# remote-camera.net
KiCad netlist of a schematic drawn in EAGLE
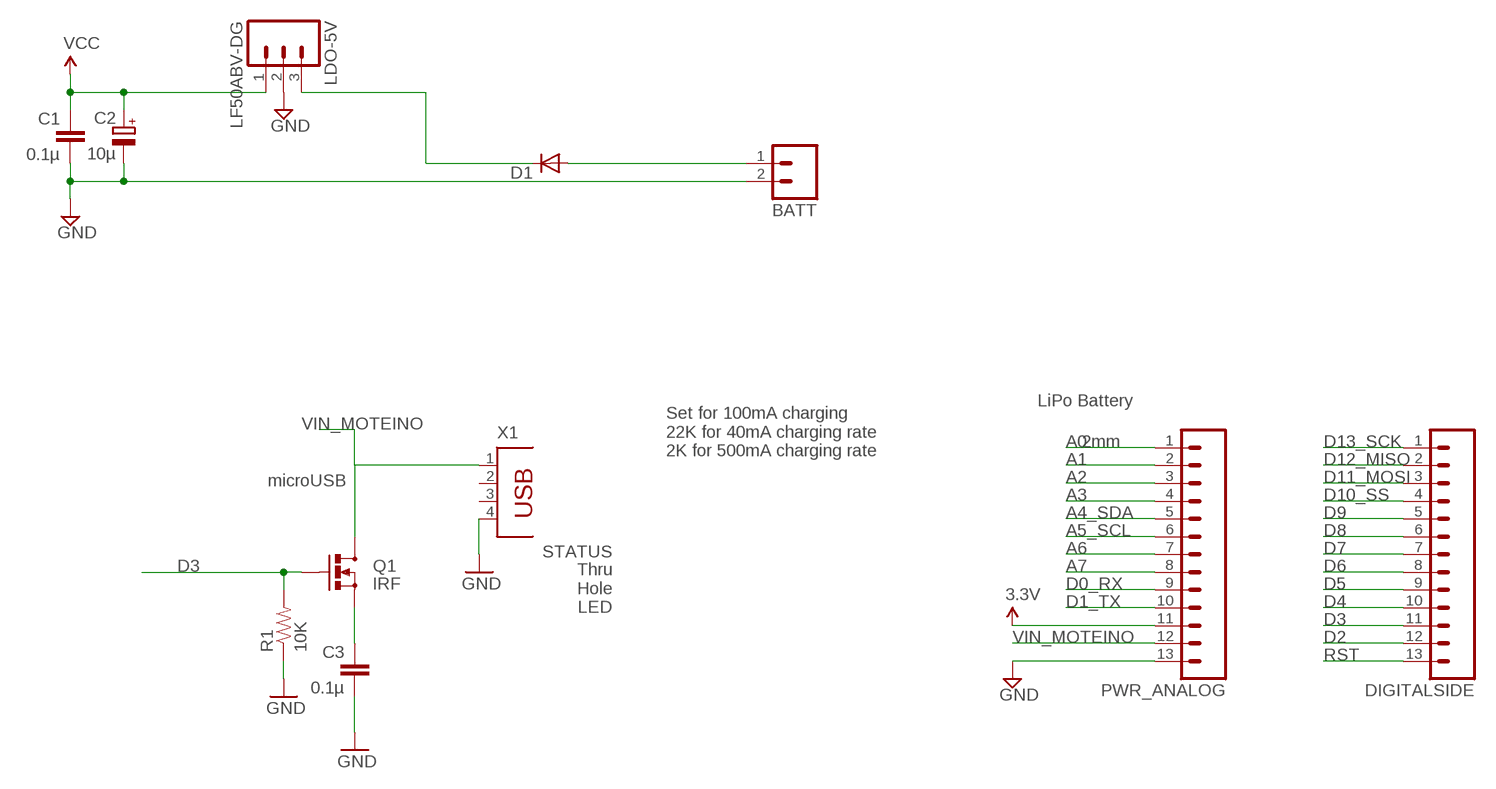
[diagram p0: schematic, sheet 1]

(export (version "E")
  (design (tool "Eeschema 10.0.6"))
  (components
    (comp (ref "BATT")
      (value "M02PTH")
      (footprint "eagle-import:1X02")
      (libsource (lib "eagle-import") (part "M02PTH"))
    )
    (comp (ref "C1")
      (value "0.1µ")
      (footprint "eagle-import:C025-024X044")
      (libsource (lib "eagle-import") (part "C-EU025-024X044"))
    )
    (comp (ref "C2")
      (value "10µ")
      (footprint "eagle-import:E1,8-4")
      (libsource (lib "eagle-import") (part "CPOL-EUE1.8-4"))
    )
    (comp (ref "C3")
      (value "0.1µ")
      (footprint "eagle-import:C025-024X044")
      (libsource (lib "eagle-import") (part "C-EU025-024X044"))
    )
    (comp (ref "D1")
      (value "DIODE-D-5")
      (footprint "eagle-import:D-5")
      (libsource (lib "eagle-import") (part "DIODE-D-5"))
    )
    (comp (ref "DIGITALSIDE")
      (value "HDR_13PINREGULAR")
      (footprint "eagle-import:1X13")
      (libsource (lib "eagle-import") (part "HDR_13PINREGULAR"))
    )
    (comp (ref "LDO-5V")
      (value "LF50ABV-DG")
      (footprint "eagle-import:1X03")
      (libsource (lib "eagle-import") (part "M03PTH"))
    )
    (comp (ref "PWR_ANALOG")
      (value "HDR_13PINREGULAR")
      (footprint "eagle-import:1X13")
      (libsource (lib "eagle-import") (part "HDR_13PINREGULAR"))
    )
    (comp (ref "Q1")
      (value "IRF")
      (footprint "eagle-import:TO220V")
      (libsource (lib "eagle-import") (part "MOSFET-NCHANNELPTH2"))
    )
    (comp (ref "R1")
      (value "10K")
      (footprint "eagle-import:AXIAL-0.3")
      (libsource (lib "eagle-import") (part "RESISTORPTH1"))
    )
    (comp (ref "X1")
      (value "PN87520")
      (footprint "eagle-import:PN87520")
      (libsource (lib "eagle-import") (part "PN87520"))
    )
  )
  (nets
    (net (code "1") (name "/A0") (class "Default")
      (node (ref "PWR_ANALOG") (pin "1") (pinfunction "1_1") (pintype "passive"))
    )
    (net (code "2") (name "/A1") (class "Default")
      (node (ref "PWR_ANALOG") (pin "2") (pinfunction "2_2") (pintype "passive"))
    )
    (net (code "3") (name "/A2") (class "Default")
      (node (ref "PWR_ANALOG") (pin "3") (pinfunction "3_3") (pintype "passive"))
    )
    (net (code "4") (name "/A3") (class "Default")
      (node (ref "PWR_ANALOG") (pin "4") (pinfunction "4_4") (pintype "passive"))
    )
    (net (code "5") (name "/A4_SDA") (class "Default")
      (node (ref "PWR_ANALOG") (pin "5") (pinfunction "5_5") (pintype "passive"))
    )
    (net (code "6") (name "/A5_SCL") (class "Default")
      (node (ref "PWR_ANALOG") (pin "6") (pinfunction "6_6") (pintype "passive"))
    )
    (net (code "7") (name "/A6") (class "Default")
      (node (ref "PWR_ANALOG") (pin "7") (pinfunction "7_7") (pintype "passive"))
    )
    (net (code "8") (name "/A7") (class "Default")
      (node (ref "PWR_ANALOG") (pin "8") (pinfunction "8_8") (pintype "passive"))
    )
    (net (code "9") (name "/D0_RX") (class "Default")
      (node (ref "PWR_ANALOG") (pin "9") (pinfunction "9_9") (pintype "passive"))
    )
    (net (code "10") (name "/D1_TX") (class "Default")
      (node (ref "PWR_ANALOG") (pin "10") (pinfunction "10_10") (pintype "passive"))
    )
    (net (code "11") (name "/D2") (class "Default")
      (node (ref "DIGITALSIDE") (pin "12") (pinfunction "12_12") (pintype "passive"))
    )
    (net (code "12") (name "/D3") (class "Default")
      (node (ref "DIGITALSIDE") (pin "11") (pinfunction "11_11") (pintype "passive"))
      (node (ref "Q1") (pin "1") (pinfunction "G_1") (pintype "passive"))
      (node (ref "R1") (pin "P$2") (pinfunction "2_P$2") (pintype "passive"))
    )
    (net (code "13") (name "/D4") (class "Default")
      (node (ref "DIGITALSIDE") (pin "10") (pinfunction "10_10") (pintype "passive"))
    )
    (net (code "14") (name "/D5") (class "Default")
      (node (ref "DIGITALSIDE") (pin "9") (pinfunction "9_9") (pintype "passive"))
    )
    (net (code "15") (name "/D6") (class "Default")
      (node (ref "DIGITALSIDE") (pin "8") (pinfunction "8_8") (pintype "passive"))
    )
    (net (code "16") (name "/D7") (class "Default")
      (node (ref "DIGITALSIDE") (pin "7") (pinfunction "7_7") (pintype "passive"))
    )
    (net (code "17") (name "/D8") (class "Default")
      (node (ref "DIGITALSIDE") (pin "6") (pinfunction "6_6") (pintype "passive"))
    )
    (net (code "18") (name "/D9") (class "Default")
      (node (ref "DIGITALSIDE") (pin "5") (pinfunction "5_5") (pintype "passive"))
    )
    (net (code "19") (name "/D10_SS") (class "Default")
      (node (ref "DIGITALSIDE") (pin "4") (pinfunction "4_4") (pintype "passive"))
    )
    (net (code "20") (name "/D11_MOSI") (class "Default")
      (node (ref "DIGITALSIDE") (pin "3") (pinfunction "3_3") (pintype "passive"))
    )
    (net (code "21") (name "/D12_MISO") (class "Default")
      (node (ref "DIGITALSIDE") (pin "2") (pinfunction "2_2") (pintype "passive"))
    )
    (net (code "22") (name "/D13_SCK") (class "Default")
      (node (ref "DIGITALSIDE") (pin "1") (pinfunction "1_1") (pintype "passive"))
    )
    (net (code "23") (name "/RST") (class "Default")
      (node (ref "DIGITALSIDE") (pin "13") (pinfunction "13_13") (pintype "passive"))
    )
    (net (code "24") (name "/VIN_MOTEINO") (class "Default")
      (node (ref "PWR_ANALOG") (pin "12") (pinfunction "12_12") (pintype "passive"))
      (node (ref "Q1") (pin "2") (pinfunction "D_2") (pintype "passive"))
      (node (ref "X1") (pin "1") (pinfunction "1_1") (pintype "passive"))
    )
    (net (code "25") (name "3.3V") (class "Default")
      (node (ref "C1") (pin "1") (pinfunction "1_1") (pintype "passive"))
      (node (ref "C2") (pin "+") (pinfunction "+_+") (pintype "passive"))
      (node (ref "LDO-5V") (pin "1") (pinfunction "1_1") (pintype "passive"))
      (node (ref "PWR_ANALOG") (pin "11") (pinfunction "11_11") (pintype "passive"))
    )
    (net (code "26") (name "GND") (class "Default")
      (node (ref "BATT") (pin "2") (pinfunction "2_2") (pintype "passive"))
      (node (ref "C1") (pin "2") (pinfunction "2_2") (pintype "passive"))
      (node (ref "C2") (pin "-") (pinfunction "-_-") (pintype "passive"))
      (node (ref "C3") (pin "2") (pinfunction "2_2") (pintype "passive"))
      (node (ref "LDO-5V") (pin "2") (pinfunction "2_2") (pintype "passive"))
      (node (ref "PWR_ANALOG") (pin "13") (pinfunction "13_13") (pintype "passive"))
      (node (ref "R1") (pin "P$1") (pinfunction "1_P$1") (pintype "passive"))
      (node (ref "X1") (pin "4") (pinfunction "4_4") (pintype "passive"))
    )
    (net (code "27") (name "Net-(BATT-Pad1)") (class "Default")
      (node (ref "BATT") (pin "1") (pinfunction "1_1") (pintype "passive"))
      (node (ref "D1") (pin "A") (pinfunction "A_A") (pintype "passive"))
    )
    (net (code "28") (name "Net-(D1-PadC)") (class "Default")
      (node (ref "D1") (pin "C") (pinfunction "C_C") (pintype "passive"))
      (node (ref "LDO-5V") (pin "3") (pinfunction "3_3") (pintype "passive"))
    )
    (net (code "29") (name "Net-(Q1-S)") (class "Default")
      (node (ref "C3") (pin "1") (pinfunction "1_1") (pintype "passive"))
      (node (ref "Q1") (pin "3") (pinfunction "S_3") (pintype "passive"))
    )
    (net (code "30") (name "unconnected-(X1-Pad2)") (class "Default")
      (node (ref "X1") (pin "2") (pinfunction "2_2") (pintype "passive"))
    )
    (net (code "31") (name "unconnected-(X1-Pad3)") (class "Default")
      (node (ref "X1") (pin "3") (pinfunction "3_3") (pintype "passive"))
    )
  )
)
